# Hyper_VAPE.net
KiCad netlist of a schematic drawn in EAGLE
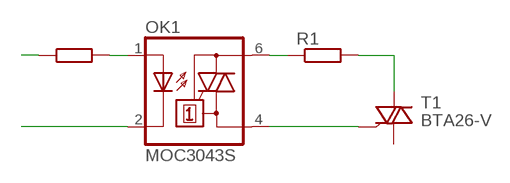
[diagram p0: schematic, sheet 1]

(export (version "E")
  (design (tool "Eeschema 10.0.6"))
  (components
    (comp (ref "OK1")
      (value "MOC3043S")
      (footprint "eagle-import:DIL6-SMD")
      (fields (field (name "MF") "FAIRCHILD SEMICONDUCTOR") (field (name "MPN") "MOC3043SM"))
      (libsource (lib "eagle-import") (part "MOC30S43"))
    )
    (comp (ref "R1")
      (value "R-EU_0411/3V")
      (footprint "eagle-import:0411V")
      (libsource (lib "eagle-import") (part "R-EU_0411/3V"))
    )
    (comp (ref "R3")
      (value "R0805")
      (footprint "eagle-import:R0805")
      (libsource (lib "eagle-import") (part "R0805"))
    )
    (comp (ref "T1")
      (value "BTA26-V")
      (footprint "eagle-import:TOP3S-1")
      (libsource (lib "eagle-import") (part "BTA26-V"))
    )
  )
  (nets
    (net (code "1") (name "Net-(OK1-A)") (class "Default")
      (node (ref "OK1") (pin "1") (pinfunction "A_1") (pintype "passive"))
      (node (ref "R3") (pin "2") (pinfunction "2_2") (pintype "passive"))
    )
    (net (code "2") (name "Net-(OK1-A1)") (class "Default")
      (node (ref "OK1") (pin "4") (pinfunction "A1_4") (pintype "passive"))
      (node (ref "T1") (pin "G") (pinfunction "G_G") (pintype "passive"))
    )
    (net (code "3") (name "Net-(OK1-A2)") (class "Default")
      (node (ref "OK1") (pin "6") (pinfunction "A2_6") (pintype "passive"))
      (node (ref "R1") (pin "1") (pinfunction "1_1") (pintype "passive"))
    )
    (net (code "4") (name "Net-(R1-Pad2)") (class "Default")
      (node (ref "R1") (pin "2") (pinfunction "2_2") (pintype "passive"))
      (node (ref "T1") (pin "A2") (pinfunction "A2_A2") (pintype "passive"))
    )
    (net (code "5") (name "unconnected-(OK1-C-Pad2)") (class "Default")
      (node (ref "OK1") (pin "2") (pinfunction "C_2") (pintype "passive"))
    )
    (net (code "6") (name "unconnected-(R3-Pad1)") (class "Default")
      (node (ref "R3") (pin "1") (pinfunction "1_1") (pintype "passive"))
    )
    (net (code "7") (name "unconnected-(T1-PadA1)") (class "Default")
      (node (ref "T1") (pin "A1") (pinfunction "A1_A1") (pintype "passive"))
    )
  )
)
